# Own_LDO3_dev_v1_0_Final_AR.net
KiCad netlist of a schematic drawn in EAGLE
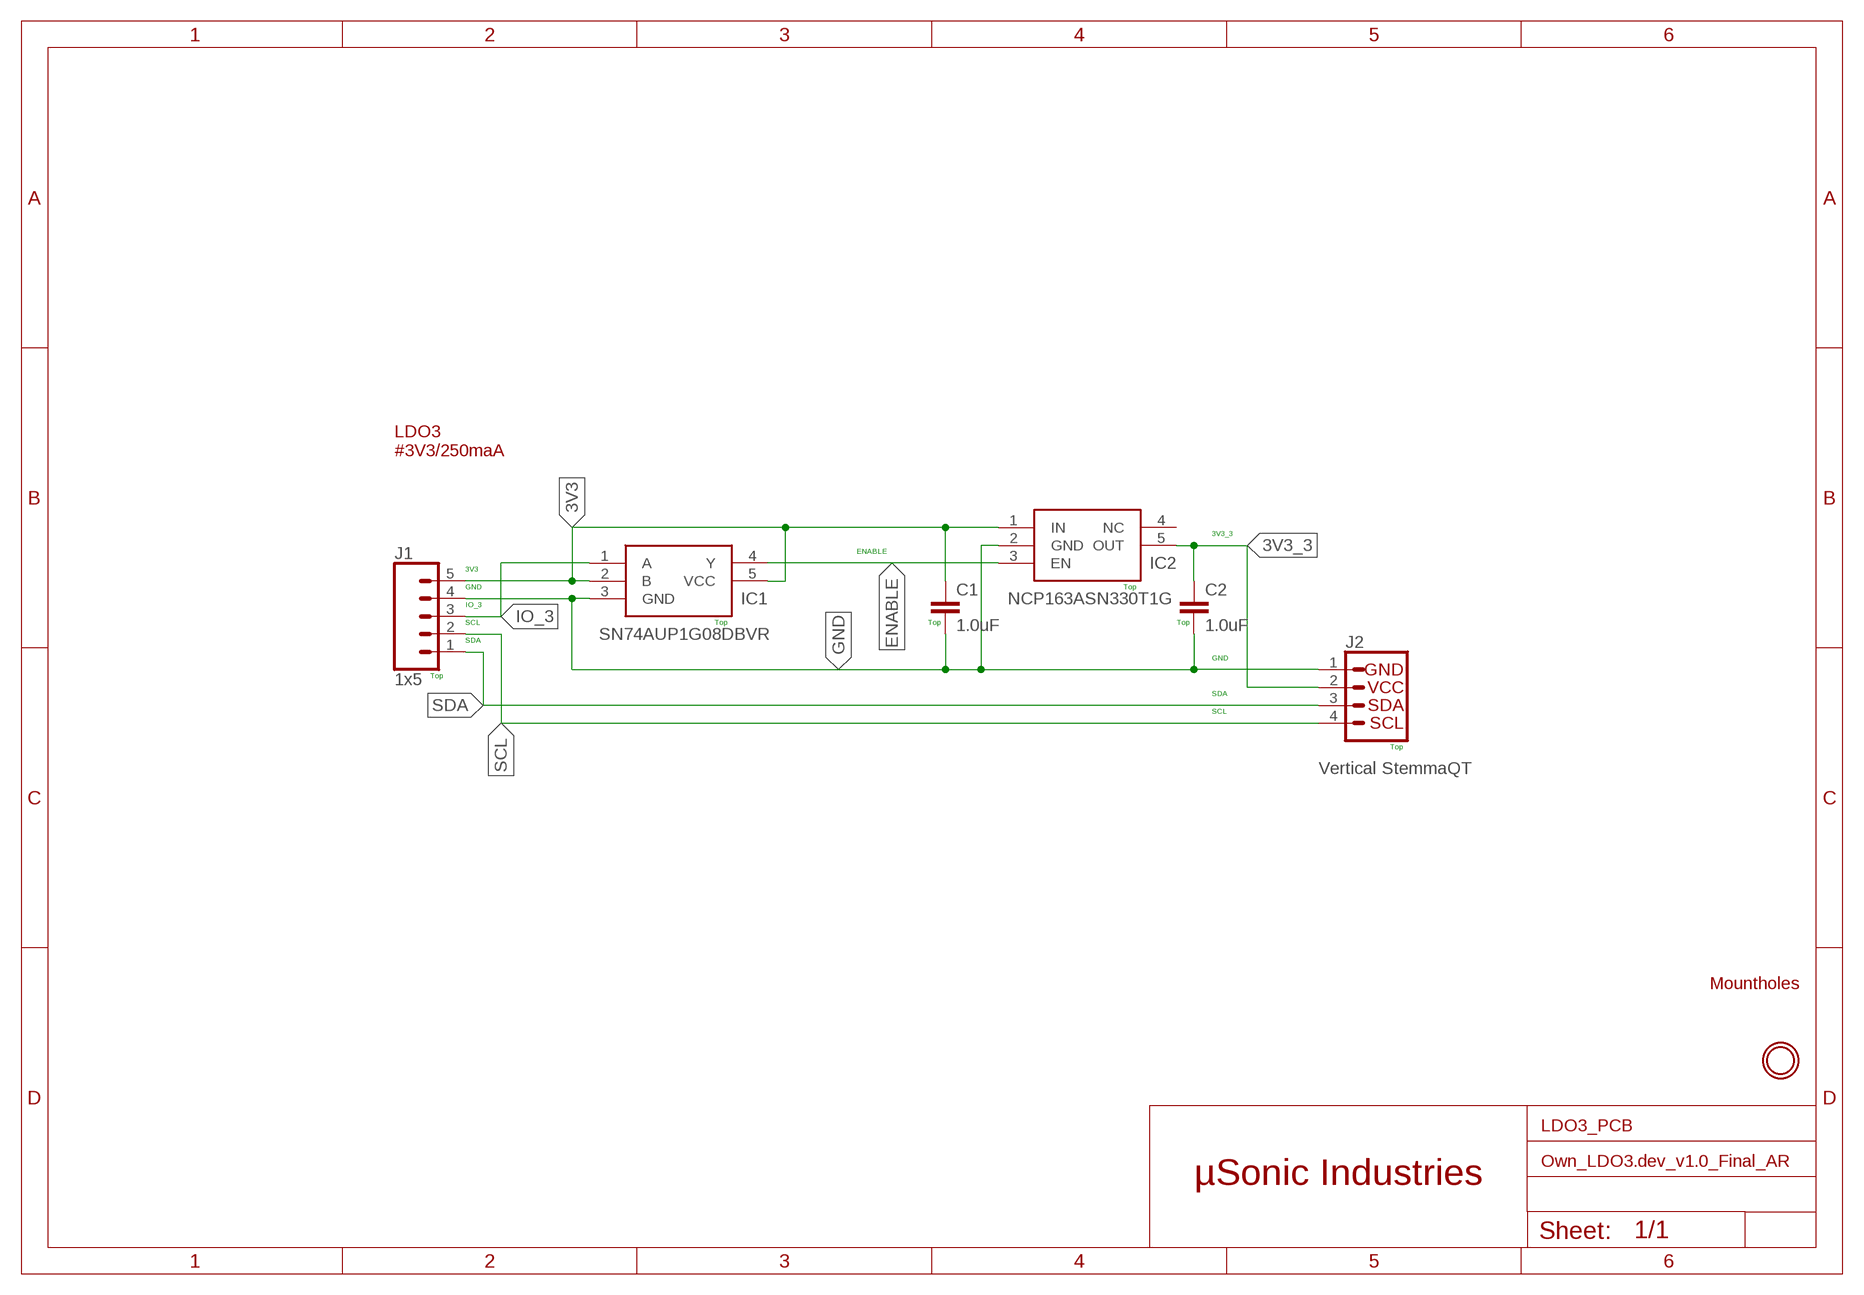
[diagram p0: schematic, sheet 1]

(export (version "E")
  (design (tool "Eeschema 10.0.6"))
  (components
    (comp (ref "C1")
      (value "1.0uF")
      (footprint "eagle-import:0805")
      (libsource (lib "eagle-import") (part "1.0UF-0805-25V-10%"))
    )
    (comp (ref "C2")
      (value "1.0uF")
      (footprint "eagle-import:0805")
      (libsource (lib "eagle-import") (part "1.0UF-0805-25V-10%"))
    )
    (comp (ref "IC1")
      (value "SN74AUP1G08DBVR")
      (footprint "eagle-import:SOT95P280X145-5N")
      (fields (field (name "MOUSER_PART_NUMBER") "595-SN74AUP1G08DBVR"))
      (libsource (lib "eagle-import") (part "SN74AUP1G08DBVR"))
    )
    (comp (ref "IC2")
      (value "NCP163ASN330T1G")
      (footprint "eagle-import:SOT95P280X145-5N")
      (fields (field (name "MOUSER_PART_NUMBER") "863-NCP163ASN330T1G"))
      (libsource (lib "eagle-import") (part "NCP163ASN330T1G"))
    )
    (comp (ref "J1")
      (value "1x5")
      (footprint "eagle-import:1X05_NO_SILK")
      (libsource (lib "eagle-import") (part "CONN_05NO_SILK"))
    )
    (comp (ref "J2")
      (value "Vertical StemmaQT")
      (footprint "eagle-import:JST04_1MM_VERT")
      (libsource (lib "eagle-import") (part "QWIIC_CONNECTOROWN"))
    )
    (comp (ref "U$1")
      (value "MOUNTINGHOLE2.5")
      (footprint "eagle-import:MOUNTINGHOLE_2.5_PLATED")
      (libsource (lib "eagle-import") (part "MOUNTINGHOLE2.5"))
    )
  )
  (nets
    (net (code "1") (name "3V3") (class "Default")
      (node (ref "C1") (pin "1") (pinfunction "1_1") (pintype "passive"))
      (node (ref "IC1") (pin "2") (pinfunction "B_2") (pintype "bidirectional"))
      (node (ref "IC1") (pin "5") (pinfunction "VCC_5") (pintype "bidirectional"))
      (node (ref "IC2") (pin "1") (pinfunction "IN_1") (pintype "bidirectional"))
      (node (ref "J1") (pin "5") (pinfunction "5_5") (pintype "passive"))
    )
    (net (code "2") (name "3V3_3") (class "Default")
      (node (ref "C2") (pin "1") (pinfunction "1_1") (pintype "passive"))
      (node (ref "IC2") (pin "5") (pinfunction "OUT_5") (pintype "bidirectional"))
      (node (ref "J2") (pin "2") (pinfunction "2_2") (pintype "power_in"))
    )
    (net (code "3") (name "ENABLE") (class "Default")
      (node (ref "IC1") (pin "4") (pinfunction "Y_4") (pintype "bidirectional"))
      (node (ref "IC2") (pin "3") (pinfunction "EN_3") (pintype "bidirectional"))
    )
    (net (code "4") (name "GND") (class "Default")
      (node (ref "C1") (pin "2") (pinfunction "2_2") (pintype "passive"))
      (node (ref "C2") (pin "2") (pinfunction "2_2") (pintype "passive"))
      (node (ref "IC1") (pin "3") (pinfunction "GND_3") (pintype "bidirectional"))
      (node (ref "IC2") (pin "2") (pinfunction "GND_2") (pintype "bidirectional"))
      (node (ref "J1") (pin "4") (pinfunction "4_4") (pintype "passive"))
      (node (ref "J2") (pin "1") (pinfunction "1_1") (pintype "power_in"))
    )
    (net (code "5") (name "IO_3") (class "Default")
      (node (ref "IC1") (pin "1") (pinfunction "A_1") (pintype "bidirectional"))
      (node (ref "J1") (pin "3") (pinfunction "3_3") (pintype "passive"))
    )
    (net (code "6") (name "SCL") (class "Default")
      (node (ref "J1") (pin "2") (pinfunction "2_2") (pintype "passive"))
      (node (ref "J2") (pin "4") (pinfunction "4_4") (pintype "passive"))
    )
    (net (code "7") (name "SDA") (class "Default")
      (node (ref "J1") (pin "1") (pinfunction "1_1") (pintype "passive"))
      (node (ref "J2") (pin "3") (pinfunction "3_3") (pintype "passive"))
    )
    (net (code "8") (name "unconnected-(IC2-NC-Pad4)") (class "Default")
      (node (ref "IC2") (pin "4") (pinfunction "NC_4") (pintype "no_connect"))
    )
  )
)
